# Power_Supplies.net
KiCad netlist of a schematic drawn in Altium Designer
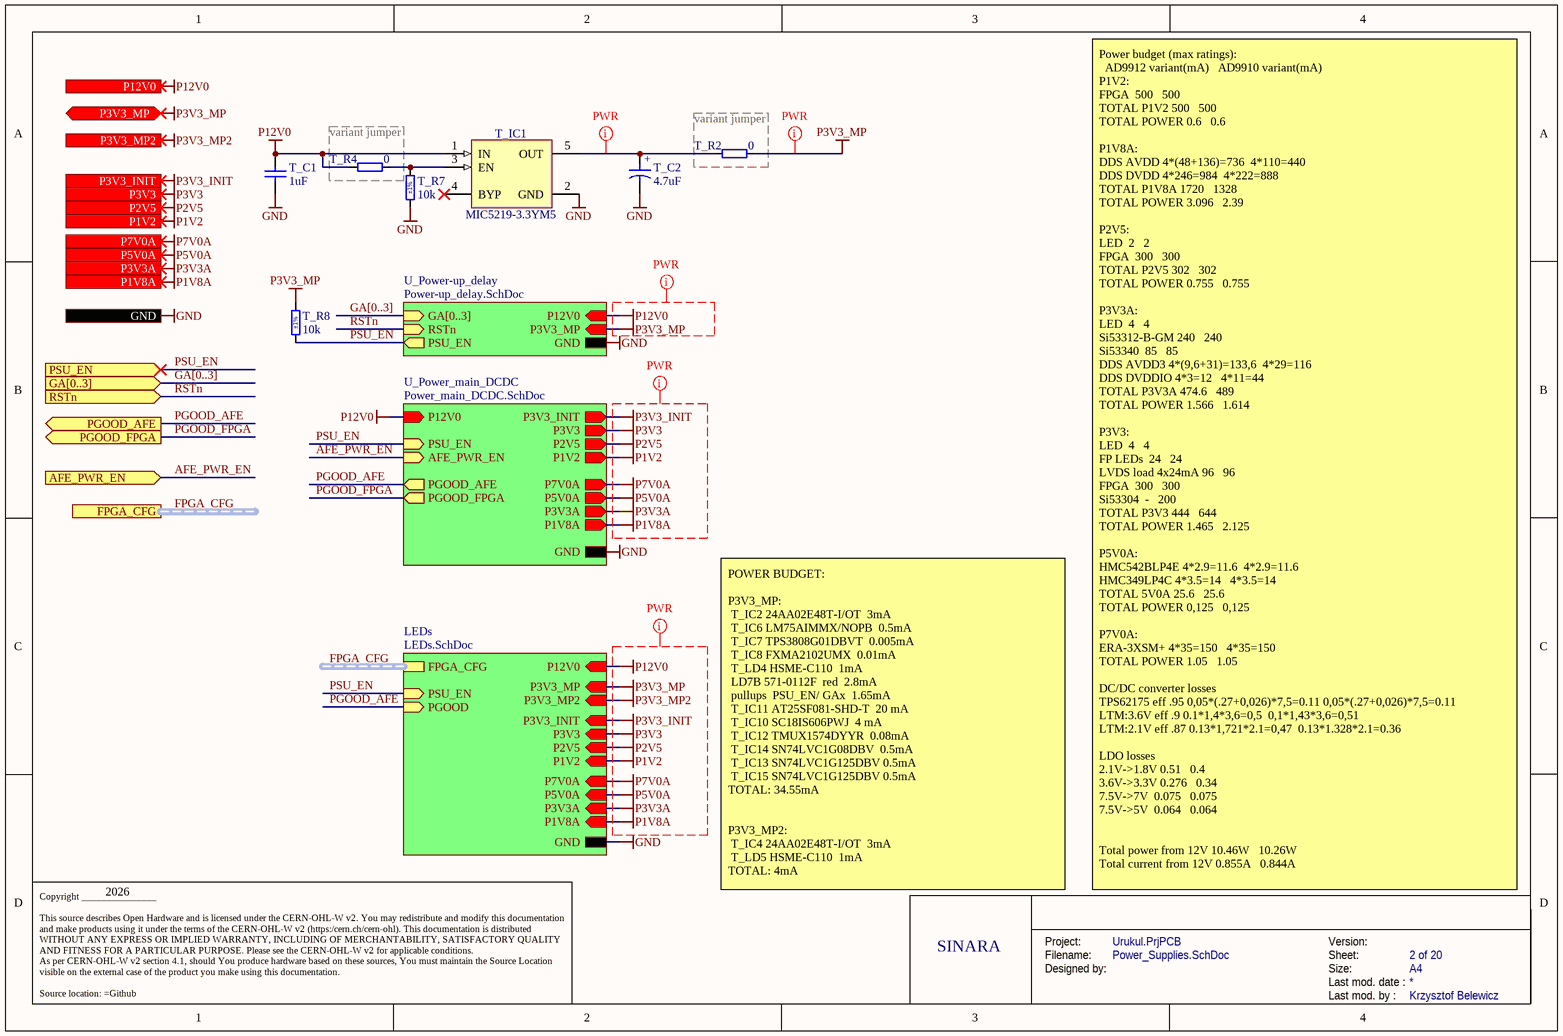
[diagram p0: Power_Supplies.SchDoc]

(export (version "E")
  (design (tool "Eeschema 10.0.6"))
  (components
    (comp (ref "T_C1")
      (value "1uF")
      (footprint "CAPC1608X87N")
      (description "Non-polarised capacitor")
      (fields
        (field (name "PART NUMBER") "CC0603_1UF_25V_10%_X7R")
        (field (name "VOLTAGE") "25V")
        (field (name "AUTHOR") "CERN DEM JLC")
      )
      (libsource (lib "Capacitors") (part "Capacitor - non polarized"))
    )
    (comp (ref "T_C2")
      (value "4.7uF")
      (footprint "CAPMP3216X180N")
      (description "Polarised capacitor")
      (fields
        (field (name "PART NUMBER") "CTE3216-18_4.7UF_10V_10%_AVX_TPSA475K010T1400")
        (field (name "VOLTAGE") "10V")
        (field (name "AUTHOR") "CERN DEM JLC")
      )
      (libsource (lib "Capacitors") (part "Capacitor - polarized"))
    )
    (comp (ref "T_IC1")
      (value "MIC5219-3.3YM5")
      (footprint "SOT95P280X145-5N")
      (description "500mA Peak Output LDO Regulator")
      (fields (field (name "MANUFACTURER") "MICROCHIP TECHNOLOGY") (field (name "AUTHOR") "CERN DEM WB"))
      (libsource (lib "ICs And Semiconductors") (part "MIC5219-X.XYM5"))
    )
    (comp (ref "T_R2")
      (value "0")
      (footprint "RESC1005X40N")
      (description "Resistor")
      (fields
        (field (name "PART NUMBER") "R0402_0R_JUMPER")
        (field (name "MANUFACTURER") "GENERIC")
        (field (name "AUTHOR") "CERN DEM JLC")
      )
      (libsource (lib "Resistors") (part "Resistor"))
    )
    (comp (ref "T_R4")
      (value "0")
      (footprint "RESC1005X40N")
      (description "Resistor")
      (fields
        (field (name "PART NUMBER") "R0402_0R_JUMPER")
        (field (name "MANUFACTURER") "GENERIC")
        (field (name "AUTHOR") "CERN DEM JLC")
      )
      (libsource (lib "Resistors") (part "Resistor"))
    )
    (comp (ref "T_R7")
      (value "10k")
      (footprint "RESC1005X40N")
      (description "Resistor - 1%")
      (fields
        (field (name "TOLERANCE") "±1%")
        (field (name "PART NUMBER") "R0402_10K_1%_0.0625W_100PPM")
        (field (name "POWER") "0.0625W")
        (field (name "AUTHOR") "CERN DEM JLC")
      )
      (libsource (lib "Resistors") (part "Resistor - 1%"))
    )
    (comp (ref "T_R8")
      (value "10k")
      (footprint "RESC1005X40N")
      (description "Resistor - 1%")
      (fields
        (field (name "TOLERANCE") "±1%")
        (field (name "PART NUMBER") "R0402_10K_1%_0.0625W_100PPM")
        (field (name "POWER") "0.0625W")
        (field (name "AUTHOR") "CERN DEM JLC")
      )
      (libsource (lib "Resistors") (part "Resistor - 1%"))
    )
  )
  (nets
    (net (code "10") (name "/PSU_EN") (class "Default")
      (node (ref "T_R8") (pin "1") (pinfunction "1_1") (pintype "passive"))
    )
    (net (code "13") (name "GND") (class "Default")
      (node (ref "T_C1") (pin "1") (pinfunction "1_1") (pintype "passive"))
      (node (ref "T_C2") (pin "2") (pinfunction "2_2") (pintype "passive"))
      (node (ref "T_IC1") (pin "2") (pinfunction "GND_2") (pintype "power_in"))
      (node (ref "T_R7") (pin "1") (pinfunction "1_1") (pintype "passive"))
    )
    (net (code "14") (name "Net-(T_IC1-EN)") (class "Default")
      (node (ref "T_IC1") (pin "3") (pinfunction "EN_3") (pintype "input"))
      (node (ref "T_R4") (pin "2") (pinfunction "2_2") (pintype "passive"))
      (node (ref "T_R7") (pin "2") (pinfunction "2_2") (pintype "passive"))
    )
    (net (code "15") (name "Net-(T_IC1-OUT)") (class "Default")
      (node (ref "T_C2") (pin "1") (pinfunction "1_1") (pintype "passive"))
      (node (ref "T_IC1") (pin "5") (pinfunction "OUT_5") (pintype "power_in"))
      (node (ref "T_R2") (pin "1") (pinfunction "1_1") (pintype "passive"))
    )
    (net (code "22") (name "P3V3_MP") (class "Default")
      (node (ref "T_R2") (pin "2") (pinfunction "2_2") (pintype "passive"))
      (node (ref "T_R8") (pin "2") (pinfunction "2_2") (pintype "passive"))
    )
    (net (code "26") (name "P12V0") (class "Default")
      (node (ref "T_C1") (pin "2") (pinfunction "2_2") (pintype "passive"))
      (node (ref "T_IC1") (pin "1") (pinfunction "IN_1") (pintype "input"))
      (node (ref "T_R4") (pin "1") (pinfunction "1_1") (pintype "passive"))
    )
    (net (code "27") (name "unconnected-(T_IC1-BYP-Pad4)") (class "Default")
      (node (ref "T_IC1") (pin "4") (pinfunction "BYP_4") (pintype "passive+no_connect"))
    )
  )
)
